# 3_3V.net
KiCad netlist of a schematic drawn in Altium Designer
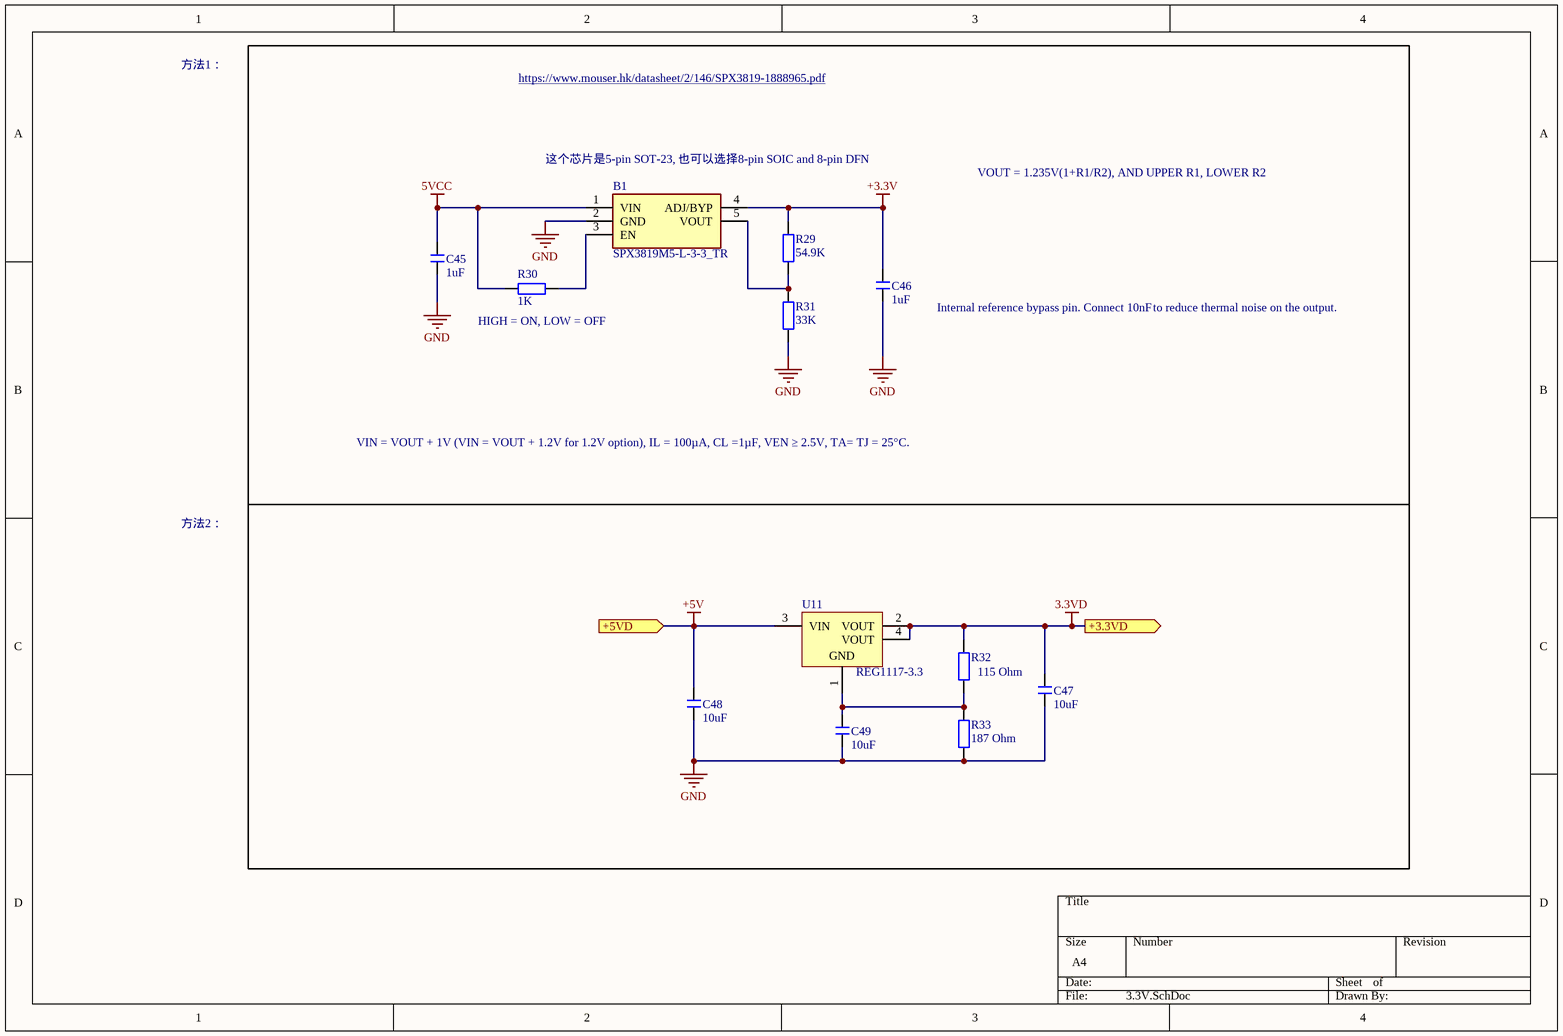
[diagram p0: 3.3V.SchDoc]

(export (version "E")
  (design (tool "Eeschema 10.0.6"))
  (components
    (comp (ref "B1")
      (value "SPX3819M5-L-3-3_TR")
      (footprint "SOT95P280X145-5N")
      (fields
        (field (name "MOUSER PART NUMBER") "701-SPX3819M5-L-33TR")
        (field (name "MANUFACTURER_PART_NUMBER") "SPX3819M5-L-3-3/TR")
      )
      (libsource (lib "SPX3819M5-L-3-3_TR") (part "SPX3819M5-L-3-3_TR"))
    )
    (comp (ref "C45")
      (value "1uF")
      (footprint "C 0805_L")
      (description "贴片电容")
      (libsource (lib "0.1 - 电阻-电容-电感") (part "C"))
    )
    (comp (ref "C46")
      (value "1uF")
      (footprint "C 0805_L")
      (description "贴片电容")
      (libsource (lib "0.1 - 电阻-电容-电感") (part "C"))
    )
    (comp (ref "C47")
      (value "10uF")
      (footprint "C 0805_L")
      (description "贴片电容")
      (libsource (lib "0.1 - 电阻-电容-电感") (part "C"))
    )
    (comp (ref "C48")
      (value "10uF")
      (footprint "C 0805_L")
      (description "贴片电容")
      (libsource (lib "0.1 - 电阻-电容-电感") (part "C"))
    )
    (comp (ref "C49")
      (value "10uF")
      (footprint "C 0805_L")
      (description "贴片电容")
      (libsource (lib "0.1 - 电阻-电容-电感") (part "C"))
    )
    (comp (ref "R29")
      (value "54.9K")
      (footprint "R 0805_L")
      (description "贴片电阻")
      (fields (field (name "版权归属") "来自淘宝 ID：黄晶宝石"))
      (libsource (lib "0.1 - 电阻-电容-电感") (part "R"))
    )
    (comp (ref "R30")
      (value "1K")
      (footprint "R 0805_L")
      (description "贴片电阻")
      (fields (field (name "版权归属") "来自淘宝 ID：黄晶宝石"))
      (libsource (lib "0.1 - 电阻-电容-电感") (part "R"))
    )
    (comp (ref "R31")
      (value "33K")
      (footprint "R 0805_L")
      (description "贴片电阻")
      (fields (field (name "版权归属") "来自淘宝 ID：黄晶宝石"))
      (libsource (lib "0.1 - 电阻-电容-电感") (part "R"))
    )
    (comp (ref "R32")
      (value "115 Ohm")
      (footprint "R 0805_L")
      (description "贴片电阻")
      (fields (field (name "版权归属") "来自淘宝 ID：黄晶宝石"))
      (libsource (lib "0.1 - 电阻-电容-电感") (part "R"))
    )
    (comp (ref "R33")
      (value "187 Ohm")
      (footprint "R 0805_L")
      (description "贴片电阻")
      (fields (field (name "版权归属") "来自淘宝 ID：黄晶宝石"))
      (libsource (lib "0.1 - 电阻-电容-电感") (part "R"))
    )
    (comp (ref "U11")
      (value "REG1117-3.3")
      (footprint "DCY0004A_M")
      (fields (field (name "MANUFACTURER") "Texas Instruments"))
      (libsource (lib "Components - 22.10.23 - 20.31") (part "CMP-0395-00549-2"))
    )
  )
  (nets
    (net (code "1") (name "+3.3V") (class "Default")
      (node (ref "B1") (pin "4") (pinfunction "ADJ/BYP_4") (pintype "passive"))
      (node (ref "C46") (pin "2") (pinfunction "2_2") (pintype "passive"))
      (node (ref "R29") (pin "2") (pinfunction "2_2") (pintype "passive"))
    )
    (net (code "2") (name "+5V") (class "Default")
      (node (ref "C48") (pin "2") (pinfunction "2_2") (pintype "passive"))
      (node (ref "U11") (pin "3") (pinfunction "VIN_3") (pintype "passive"))
    )
    (net (code "3") (name "3.3VD") (class "Default")
      (node (ref "C47") (pin "2") (pinfunction "2_2") (pintype "passive"))
      (node (ref "R32") (pin "2") (pinfunction "2_2") (pintype "passive"))
      (node (ref "U11") (pin "2") (pinfunction "VOUT_2") (pintype "passive"))
      (node (ref "U11") (pin "4") (pinfunction "VOUT_4") (pintype "passive"))
    )
    (net (code "4") (name "5VCC") (class "Default")
      (node (ref "B1") (pin "1") (pinfunction "VIN_1") (pintype "passive"))
      (node (ref "C45") (pin "2") (pinfunction "2_2") (pintype "passive"))
      (node (ref "R30") (pin "1") (pinfunction "1_1") (pintype "passive"))
    )
    (net (code "5") (name "GND") (class "Default")
      (node (ref "B1") (pin "2") (pinfunction "GND_2") (pintype "passive"))
      (node (ref "C45") (pin "1") (pinfunction "1_1") (pintype "passive"))
      (node (ref "C46") (pin "1") (pinfunction "1_1") (pintype "passive"))
      (node (ref "C47") (pin "1") (pinfunction "1_1") (pintype "passive"))
      (node (ref "C48") (pin "1") (pinfunction "1_1") (pintype "passive"))
      (node (ref "C49") (pin "1") (pinfunction "1_1") (pintype "passive"))
      (node (ref "R31") (pin "1") (pinfunction "1_1") (pintype "passive"))
      (node (ref "R33") (pin "1") (pinfunction "1_1") (pintype "passive"))
    )
    (net (code "6") (name "Net-(B1-EN)") (class "Default")
      (node (ref "B1") (pin "3") (pinfunction "EN_3") (pintype "passive"))
      (node (ref "R30") (pin "2") (pinfunction "2_2") (pintype "passive"))
    )
    (net (code "7") (name "Net-(B1-VOUT)") (class "Default")
      (node (ref "B1") (pin "5") (pinfunction "VOUT_5") (pintype "passive"))
      (node (ref "R29") (pin "1") (pinfunction "1_1") (pintype "passive"))
      (node (ref "R31") (pin "2") (pinfunction "2_2") (pintype "passive"))
    )
    (net (code "8") (name "Net-(U11-GND)") (class "Default")
      (node (ref "C49") (pin "2") (pinfunction "2_2") (pintype "passive"))
      (node (ref "R32") (pin "1") (pinfunction "1_1") (pintype "passive"))
      (node (ref "R33") (pin "2") (pinfunction "2_2") (pintype "passive"))
      (node (ref "U11") (pin "1") (pinfunction "GND_1") (pintype "power_in"))
    )
  )
)
